# TOD.net
KiCad netlist of a schematic drawn in Altium Designer
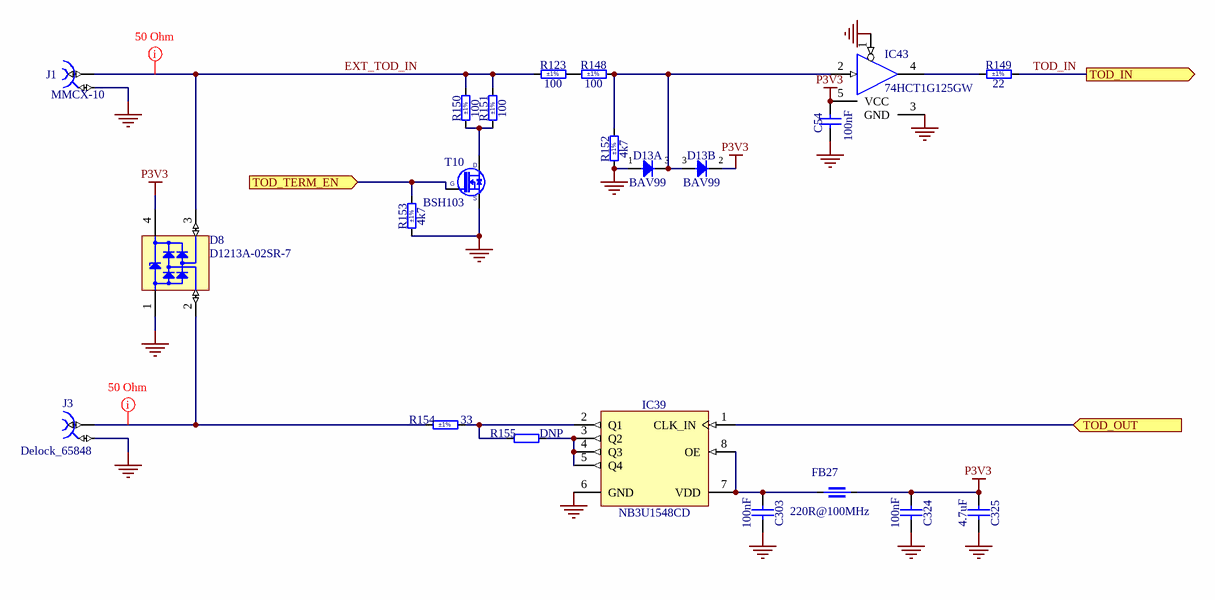
[diagram p0: TOD.SchDoc]

(export (version "E")
  (design (tool "Eeschema 10.0.6"))
  (components
    (comp (ref "C54")
      (value "100nF")
      (footprint "CAPC0603X33N")
      (description "Non-polarised capacitor")
      (fields
        (field (name "PART NUMBER") "CC0201_100NF_6.3V_10%_X5R")
        (field (name "VOLTAGE") "6.3V")
        (field (name "AUTHOR") "CERN DEM JLC")
      )
      (libsource (lib "Capacitors") (part "Capacitor - non polarized"))
    )
    (comp (ref "C303")
      (value "100nF")
      (footprint "CAPC0603X33N")
      (description "Non-polarised capacitor")
      (fields
        (field (name "PART NUMBER") "CC0201_100NF_6.3V_10%_X5R")
        (field (name "VOLTAGE") "6.3V")
        (field (name "AUTHOR") "CERN DEM JLC")
      )
      (libsource (lib "Capacitors") (part "Capacitor - non polarized"))
    )
    (comp (ref "C324")
      (value "100nF")
      (footprint "CAPC0603X33N")
      (description "Non-polarised capacitor")
      (fields
        (field (name "PART NUMBER") "CC0201_100NF_6.3V_10%_X5R")
        (field (name "VOLTAGE") "6.3V")
        (field (name "AUTHOR") "CERN DEM JLC")
      )
      (libsource (lib "Capacitors") (part "Capacitor - non polarized"))
    )
    (comp (ref "C325")
      (value "4.7uF")
      (footprint "CAPC1005X55N")
      (description "Non-polarised capacitor")
      (fields
        (field (name "PART NUMBER") "CC0402_4.7UF_6.3V_20%_X5R")
        (field (name "VOLTAGE") "6.3V")
        (field (name "AUTHOR") "CERN DEM JLC")
      )
      (libsource (lib "Capacitors") (part "Capacitor - non polarized"))
    )
    (comp (ref "D8")
      (value "D1213A-02SR-7")
      (footprint "SOT190P238X100-4N")
      (description "D1213A-02SR Series 400 mW Uni-Directional Surface Mount TVS Diode - SOT-143")
      (libsource (lib "TechnoSystem Workspace") (part "D1213A-02SR-7"))
    )
    (comp (ref "D13")
      (value "BAV99")
      (footprint "SOT95P240X110-3N")
      (description "Serial Diode")
      (fields
        (field (name "VOLTAGE") "70V")
        (field (name "POWER") "350mW")
        (field (name "AUTHOR") "CERN DEM JLC")
      )
      (libsource (lib "ICs And Semiconductors") (part "Diode x2 A1C3_A3C2"))
    )
    (comp (ref "FB27")
      (value "220R@100MHz")
      (footprint "INDC1608X95N")
      (fields
        (field (name "TOLERANCE") "±25%")
        (field (name "PART NUMBER") "IND0603_MURATA_BLM18SG221TN1")
        (field (name "POWER") "2.5A")
        (field (name "AUTHOR") "CERN DEM MR")
      )
      (libsource (lib "Inductors & Transformers") (part "Ferrite Bead"))
    )
    (comp (ref "IC39")
      (value "NB3U1548CD")
      (footprint "SOIC127P600X175-8N")
      (description "3.3V/2.5V/1.8V/1.5V 160 MHz 1:4 LVCMOS/LVTTL Low Skew Over Voltage Tolerant Fanout Buffer")
      (fields (field (name "MANUFACTURER") "ON SEMICONDUCTOR") (field (name "AUTHOR") "CERN DEM HF"))
      (libsource (lib "ICs And Semiconductors") (part "NB3U1548C"))
    )
    (comp (ref "IC43")
      (value "74HCT1G125GW")
      (footprint "SOT65P210X110-5N")
      (description "Single Bus Buffer Gate With 3-State Output")
      (fields (field (name "MANUFACTURER") "NEXPERIA") (field (name "AUTHOR") "CERN DEM JMW"))
      (libsource (lib "ICs And Semiconductors") (part "741G125"))
    )
    (comp (ref "J1")
      (value "MMCX-10")
      (footprint "SAMTEC_MMCX-J-P-H-ST-TH1")
      (fields (field (name "MANUFACTURER") "Ninigi") (field (name "AUTHOR") "GK"))
      (libsource (lib "Connectors") (part "CON_MMCX_V"))
    )
    (comp (ref "J3")
      (value "Delock_65848")
      (footprint "Delock_65848")
      (description "SMA connector Delock 65848")
      (libsource (lib "TechnoSystem Workspace") (part "Coax_1Female_1Shield"))
    )
    (comp (ref "R123")
      (value "100")
      (footprint "RESC1005X40N")
      (description "Resistor - 1%")
      (fields
        (field (name "TOLERANCE") "±1%")
        (field (name "PART NUMBER") "R0402_100R_1%_0.0625W_100PPM")
        (field (name "POWER") "0.0625W")
        (field (name "AUTHOR") "CERN DEM JLC")
      )
      (libsource (lib "Resistors") (part "Resistor - 1%"))
    )
    (comp (ref "R148")
      (value "100")
      (footprint "RESC1005X40N")
      (description "Resistor - 1%")
      (fields
        (field (name "TOLERANCE") "±1%")
        (field (name "PART NUMBER") "R0402_100R_1%_0.0625W_100PPM")
        (field (name "POWER") "0.0625W")
        (field (name "AUTHOR") "CERN DEM JLC")
      )
      (libsource (lib "Resistors") (part "Resistor - 1%"))
    )
    (comp (ref "R149")
      (value "22")
      (footprint "RESC1005X40N")
      (description "Resistor - 1%")
      (fields
        (field (name "TOLERANCE") "±1%")
        (field (name "PART NUMBER") "R0402_22R_1%_0.0625W_100PPM")
        (field (name "POWER") "0.0625W")
        (field (name "AUTHOR") "CERN DEM JLC")
      )
      (libsource (lib "Resistors") (part "Resistor - 1%"))
    )
    (comp (ref "R150")
      (value "100")
      (footprint "RESC1005X40N")
      (description "Resistor - 1%")
      (fields
        (field (name "TOLERANCE") "±1%")
        (field (name "PART NUMBER") "R0402_100R_1%_0.0625W_100PPM")
        (field (name "POWER") "0.0625W")
        (field (name "AUTHOR") "CERN DEM JLC")
      )
      (libsource (lib "Resistors") (part "Resistor - 1%"))
    )
    (comp (ref "R151")
      (value "100")
      (footprint "RESC1005X40N")
      (description "Resistor - 1%")
      (fields
        (field (name "TOLERANCE") "±1%")
        (field (name "PART NUMBER") "R0402_100R_1%_0.0625W_100PPM")
        (field (name "POWER") "0.0625W")
        (field (name "AUTHOR") "CERN DEM JLC")
      )
      (libsource (lib "Resistors") (part "Resistor - 1%"))
    )
    (comp (ref "R152")
      (value "4k7")
      (footprint "RESC1005X40N")
      (description "Resistor - 1%")
      (fields
        (field (name "TOLERANCE") "±1%")
        (field (name "PART NUMBER") "R0402_4K7_1%_0.0625W_100PPM")
        (field (name "POWER") "0.0625W")
        (field (name "AUTHOR") "CERN DEM JLC")
      )
      (libsource (lib "Resistors") (part "Resistor - 1%"))
    )
    (comp (ref "R153")
      (value "4k7")
      (footprint "RESC1005X40N")
      (description "Resistor - 1%")
      (fields
        (field (name "TOLERANCE") "±1%")
        (field (name "PART NUMBER") "R0402_4K7_1%_0.0625W_100PPM")
        (field (name "POWER") "0.0625W")
        (field (name "AUTHOR") "CERN DEM JLC")
      )
      (libsource (lib "Resistors") (part "Resistor - 1%"))
    )
    (comp (ref "R154")
      (value "33")
      (footprint "RESC2012X60N")
      (description "Resistor - 1%")
      (fields
        (field (name "PART NUMBER") "R0805_33R_1%_0.125W_100PPM")
        (field (name "MANUFACTURER") "GENERIC")
        (field (name "TOLERANCE") "±1%")
        (field (name "AUTHOR") "CERN DEM JLC")
      )
      (libsource (lib "Resistors") (part "Resistor - 1%"))
    )
    (comp (ref "R155")
      (value "DNP")
      (footprint "RESC1005X40N")
      (description "Resistor")
      (fields
        (field (name "PART NUMBER") "R0402_0R_JUMPER")
        (field (name "MANUFACTURER") "GENERIC")
        (field (name "AUTHOR") "CERN DEM JLC")
      )
      (libsource (lib "Resistors") (part "Resistor"))
    )
    (comp (ref "T10")
      (value "BSH103")
      (footprint "SOT95P230X110-3N")
      (description "N-CHANNEL MOSFET WITH DIODE")
      (fields (field (name "MANUFACTURER") "NEXPERIA") (field (name "AUTHOR") "CERN DEM JLC"))
      (libsource (lib "ICs And Semiconductors") (part "N-MOSFET-D 1G 2S 3D"))
    )
  )
  (nets
    (net (code "1") (name "/EXT_TOD_IN") (class "Default")
      (node (ref "D8") (pin "3") (pinfunction "I/O2_3") (pintype "bidirectional"))
      (node (ref "J1") (pin "1") (pinfunction "1_1") (pintype "bidirectional"))
      (node (ref "R123") (pin "1") (pinfunction "1_1") (pintype "passive"))
      (node (ref "R150") (pin "2") (pinfunction "2_2") (pintype "passive"))
      (node (ref "R151") (pin "2") (pinfunction "2_2") (pintype "passive"))
    )
    (net (code "2") (name "/TOD_IN") (class "Default")
      (node (ref "R149") (pin "2") (pinfunction "2_2") (pintype "passive"))
    )
    (net (code "3") (name "/TOD_OUT") (class "Default")
      (node (ref "IC39") (pin "1") (pinfunction "CLK_IN_1") (pintype "input"))
    )
    (net (code "4") (name "/TOD_TERM_EN") (class "Default")
      (node (ref "R153") (pin "2") (pinfunction "2_2") (pintype "passive"))
      (node (ref "T10") (pin "1") (pinfunction "G_1") (pintype "passive"))
    )
    (net (code "5") (name "GND") (class "Default")
      (node (ref "C303") (pin "1") (pinfunction "1_1") (pintype "passive"))
      (node (ref "C324") (pin "1") (pinfunction "1_1") (pintype "passive"))
      (node (ref "C325") (pin "1") (pinfunction "1_1") (pintype "passive"))
      (node (ref "C54") (pin "1") (pinfunction "1_1") (pintype "passive"))
      (node (ref "D13") (pin "1") (pinfunction "A_1") (pintype "passive"))
      (node (ref "D8") (pin "1") (pinfunction "GND_1") (pintype "power_in"))
      (node (ref "IC39") (pin "6") (pinfunction "GND_6") (pintype "power_in"))
      (node (ref "IC43") (pin "1") (pinfunction "~{G}_1") (pintype "input"))
      (node (ref "IC43") (pin "3") (pinfunction "GND_3") (pintype "power_in"))
      (node (ref "J1") (pin "2") (pinfunction "2_2") (pintype "bidirectional"))
      (node (ref "J3") (pin "2") (pinfunction "2_2") (pintype "bidirectional"))
      (node (ref "R152") (pin "1") (pinfunction "1_1") (pintype "passive"))
      (node (ref "R153") (pin "1") (pinfunction "1_1") (pintype "passive"))
      (node (ref "T10") (pin "2") (pinfunction "S_2") (pintype "passive"))
    )
    (net (code "6") (name "Net-(D8-I{slash}O1)") (class "Default")
      (node (ref "D8") (pin "2") (pinfunction "I/O1_2") (pintype "bidirectional"))
      (node (ref "J3") (pin "1") (pinfunction "1_1") (pintype "bidirectional"))
      (node (ref "R154") (pin "1") (pinfunction "1_1") (pintype "passive"))
    )
    (net (code "7") (name "Net-(D13A-COMAC)") (class "Default")
      (node (ref "D13") (pin "3") (pinfunction "COMAC_3") (pintype "passive"))
      (node (ref "IC43") (pin "2") (pinfunction "IN_2") (pintype "input"))
      (node (ref "R148") (pin "2") (pinfunction "2_2") (pintype "passive"))
      (node (ref "R152") (pin "2") (pinfunction "2_2") (pintype "passive"))
    )
    (net (code "8") (name "Net-(IC39-OE)") (class "Default")
      (node (ref "C303") (pin "2") (pinfunction "2_2") (pintype "passive"))
      (node (ref "FB27") (pin "2") (pinfunction "2_2") (pintype "passive"))
      (node (ref "IC39") (pin "7") (pinfunction "VDD_7") (pintype "power_in"))
      (node (ref "IC39") (pin "8") (pinfunction "OE_8") (pintype "input"))
    )
    (net (code "9") (name "Net-(IC39-Q1)") (class "Default")
      (node (ref "IC39") (pin "2") (pinfunction "Q1_2") (pintype "output"))
      (node (ref "R154") (pin "2") (pinfunction "2_2") (pintype "passive"))
      (node (ref "R155") (pin "1") (pinfunction "1_1") (pintype "passive"))
    )
    (net (code "10") (name "Net-(IC39-Q2)") (class "Default")
      (node (ref "IC39") (pin "3") (pinfunction "Q2_3") (pintype "output"))
      (node (ref "IC39") (pin "4") (pinfunction "Q3_4") (pintype "output"))
      (node (ref "IC39") (pin "5") (pinfunction "Q4_5") (pintype "output"))
      (node (ref "R155") (pin "2") (pinfunction "2_2") (pintype "passive"))
    )
    (net (code "11") (name "Net-(IC43-OUT)") (class "Default")
      (node (ref "IC43") (pin "4") (pinfunction "OUT_4") (pintype "tri_state"))
      (node (ref "R149") (pin "1") (pinfunction "1_1") (pintype "passive"))
    )
    (net (code "12") (name "Net-(R123-Pad2)") (class "Default")
      (node (ref "R123") (pin "2") (pinfunction "2_2") (pintype "passive"))
      (node (ref "R148") (pin "1") (pinfunction "1_1") (pintype "passive"))
    )
    (net (code "13") (name "Net-(T10-D)") (class "Default")
      (node (ref "R150") (pin "1") (pinfunction "1_1") (pintype "passive"))
      (node (ref "R151") (pin "1") (pinfunction "1_1") (pintype "passive"))
      (node (ref "T10") (pin "3") (pinfunction "D_3") (pintype "passive"))
    )
    (net (code "14") (name "P3V3") (class "Default")
      (node (ref "C324") (pin "2") (pinfunction "2_2") (pintype "passive"))
      (node (ref "C325") (pin "2") (pinfunction "2_2") (pintype "passive"))
      (node (ref "C54") (pin "2") (pinfunction "2_2") (pintype "passive"))
      (node (ref "D13") (pin "2") (pinfunction "C_2") (pintype "passive"))
      (node (ref "D8") (pin "4") (pinfunction "VCC_4") (pintype "power_in"))
      (node (ref "FB27") (pin "1") (pinfunction "1_1") (pintype "passive"))
      (node (ref "IC43") (pin "5") (pinfunction "VCC_5") (pintype "power_in"))
    )
  )
)
